# RS485.net
KiCad netlist of a schematic drawn in Altium Designer
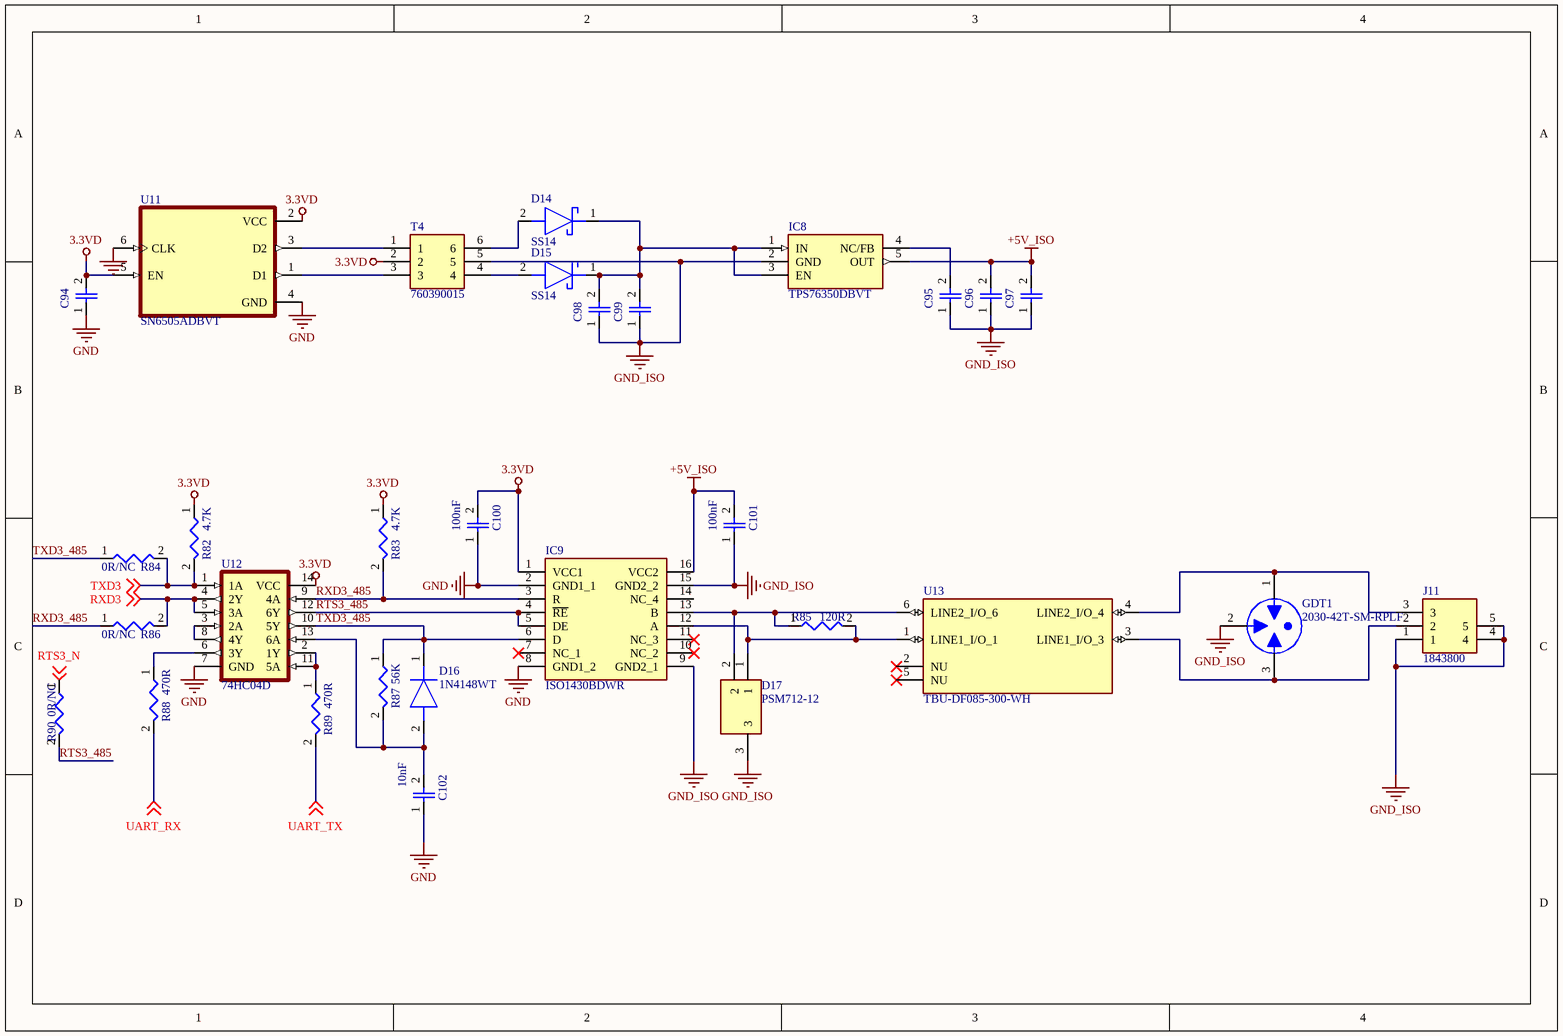
[diagram p0: RS485.SchDoc]

(export (version "E")
  (design (tool "Eeschema 10.0.6"))
  (components
    (comp (ref "C94")
      (value "10uF,0805")
      (footprint "0805-C")
      (libsource (lib "OOLITEV8_0_2-DEV-V1_1_17") (part "CAP"))
    )
    (comp (ref "C95")
      (value "10nF,0603/NC")
      (footprint "0603-C")
      (libsource (lib "OOLITEV8_0_2-DEV-V1_1_17") (part "CAP"))
    )
    (comp (ref "C96")
      (value "10uF,0805")
      (footprint "0805-C")
      (libsource (lib "OOLITEV8_0_2-DEV-V1_1_17") (part "CAP"))
    )
    (comp (ref "C97")
      (value "0.1uF,0603")
      (footprint "0603-C")
      (libsource (lib "OOLITEV8_0_2-DEV-V1_1_17") (part "CAP"))
    )
    (comp (ref "C98")
      (value "10uF,0805")
      (footprint "0805-C")
      (libsource (lib "OOLITEV8_0_2-DEV-V1_1_17") (part "CAP"))
    )
    (comp (ref "C99")
      (value "0.1uF,0603")
      (footprint "0603-C")
      (libsource (lib "OOLITEV8_0_2-DEV-V1_1_17") (part "CAP"))
    )
    (comp (ref "C100")
      (value "100nF")
      (footprint "0603-C")
      (libsource (lib "OOLITEV8_0_2-DEV-V1_1_17") (part "CAP"))
    )
    (comp (ref "C101")
      (value "100nF")
      (footprint "0603-C")
      (libsource (lib "OOLITEV8_0_2-DEV-V1_1_17") (part "CAP"))
    )
    (comp (ref "C102")
      (value "10nF")
      (footprint "0603-C")
      (libsource (lib "OOLITEV8_0_2-DEV-V1_1_17") (part "CAP"))
    )
    (comp (ref "D14")
      (value "SS14")
      (footprint "SamacSys:DIOM5127X261N")
      (description "Schottky Diode")
      (libsource (lib "*") (part "SS14"))
    )
    (comp (ref "D15")
      (value "SS14")
      (footprint "SamacSys:DIOM5127X261N")
      (description "Schottky Diode")
      (libsource (lib "*") (part "SS14"))
    )
    (comp (ref "D16")
      (value "1N4148WT")
      (footprint "SamacSys:SODFL1608X70N")
      (description "Diode")
      (libsource (lib "*") (part "1N4148WT"))
    )
    (comp (ref "D17")
      (value "PSM712-12")
      (footprint "SamacSys:PSM71212")
      (description "TVS Diode (Bi-directional)")
      (libsource (lib "*") (part "PSM712-12"))
    )
    (comp (ref "GDT1")
      (value "2030-42T-SM-RPLF")
      (footprint "2030-42T-SM-RPLF")
      (description "Gas Discharge Tube 90V 10000A _10kA_ 3 Pole Through Hole")
      (fields (field (name "MF") "Littelfuse Inc.") (field (name "MP") "SL1021A090R"))
      (libsource (lib "2030-42T-SM-RPLF") (part "2030-42T-SM-RPLF"))
    )
    (comp (ref "IC8")
      (value "TPS76350DBVT")
      (footprint "SamacSys:SOT95P280X145-5N")
      (description "Integrated Circuit")
      (fields (field (name "MOUSER PART NUMBER") "595-TPS76350DBVT"))
      (libsource (lib "*") (part "TPS76350DBVT"))
    )
    (comp (ref "IC9")
      (value "ISO1430BDWR")
      (footprint "SamacSys:SOIC127P1030X265-16N")
      (description "Integrated Circuit")
      (fields (field (name "MOUSER PART NUMBER") "595-ISO1430BDWR"))
      (libsource (lib "*") (part "ISO1430BDWR"))
    )
    (comp (ref "J11")
      (value "1843800")
      (footprint "SamacSys:1843800")
      (description "Connector")
      (fields (field (name "MOUSER PART NUMBER") "651-1843800"))
      (libsource (lib "*") (part "1843800"))
    )
    (comp (ref "R82")
      (value "4.7K")
      (footprint "0603-R")
      (libsource (lib "OOLITEV8_0_2-DEV-V1_1_17") (part "Res"))
    )
    (comp (ref "R83")
      (value "4.7K")
      (footprint "0603-R")
      (libsource (lib "OOLITEV8_0_2-DEV-V1_1_17") (part "Res"))
    )
    (comp (ref "R84")
      (value "0R/NC")
      (footprint "0603-R")
      (libsource (lib "OOLITEV8_0_2-DEV-V1_1_17") (part "Res"))
    )
    (comp (ref "R85")
      (value "120R")
      (footprint "0603-R")
      (libsource (lib "OOLITEV8_0_2-DEV-V1_1_17") (part "Res"))
    )
    (comp (ref "R86")
      (value "0R/NC")
      (footprint "0603-R")
      (libsource (lib "OOLITEV8_0_2-DEV-V1_1_17") (part "Res"))
    )
    (comp (ref "R87")
      (value "56K")
      (footprint "0603-R")
      (libsource (lib "OOLITEV8_0_2-DEV-V1_1_17") (part "Res"))
    )
    (comp (ref "R88")
      (value "470R")
      (footprint "0603-R")
      (libsource (lib "OOLITEV8_0_2-DEV-V1_1_17") (part "Res"))
    )
    (comp (ref "R89")
      (value "470R")
      (footprint "0603-R")
      (libsource (lib "OOLITEV8_0_2-DEV-V1_1_17") (part "Res"))
    )
    (comp (ref "R90")
      (value "0R/NC")
      (footprint "0603-R")
      (libsource (lib "OOLITEV8_0_2-DEV-V1_1_17") (part "Res"))
    )
    (comp (ref "T4")
      (value "760390015")
      (footprint "SamacSys:760390015")
      (description "Transformer")
      (fields (field (name "MOUSER PART NUMBER") "710-760390015"))
      (libsource (lib "*") (part "760390015"))
    )
    (comp (ref "U11")
      (value "SN6505ADBVT")
      (footprint "SOT95P280X145-6N")
      (fields
        (field (name "MF") "Texas Instruments")
        (field (name "BUYPART") "https://www.snapeda.com/parts/SN6505ADBVT/Texas%20Instruments/view-part/779078/?ref=eda")
      )
      (libsource (lib "SN6505ADBVT") (part "SN6505ADBVT"))
    )
    (comp (ref "U12")
      (value "74HC04D")
      (footprint "SOIC127P600X175-14N")
      (description "Inverter IC 6 Channel 14-SOIC")
      (fields (field (name "MF") "Toshiba"))
      (libsource (lib "74HC04D") (part "74HC04D"))
    )
    (comp (ref "U13")
      (value "TBU-DF085-300-WH")
      (footprint "IC_TBU-DF085-300-WH")
      (description "DUAL BI-DIR TBU 850V 300MA")
      (fields (field (name "MF") "Bourns Inc."))
      (libsource (lib "TBU-DF085-300-WH") (part "TBU-DF085-300-WH"))
    )
  )
  (nets
    (net (code "1") (name "+5V_ISO") (class "Default")
      (node (ref "C101") (pin "2") (pinfunction "2_2") (pintype "passive"))
      (node (ref "C96") (pin "2") (pinfunction "2_2") (pintype "passive"))
      (node (ref "C97") (pin "2") (pinfunction "2_2") (pintype "passive"))
      (node (ref "IC8") (pin "5") (pinfunction "OUT_5") (pintype "output"))
      (node (ref "IC9") (pin "16") (pinfunction "VCC2_16") (pintype "passive"))
    )
    (net (code "2") (name "/RTS3_485") (class "Default")
      (node (ref "IC9") (pin "4") (pinfunction "~{RE}_4") (pintype "passive"))
      (node (ref "IC9") (pin "5") (pinfunction "DE_5") (pintype "passive"))
      (node (ref "R90") (pin "2") (pinfunction "2_2") (pintype "passive"))
      (node (ref "U12") (pin "12") (pinfunction "6Y_12") (pintype "output"))
    )
    (net (code "3") (name "/RXD3_485") (class "Default")
      (node (ref "IC9") (pin "3") (pinfunction "R_3") (pintype "passive"))
      (node (ref "R83") (pin "2") (pinfunction "2_2") (pintype "passive"))
      (node (ref "R86") (pin "1") (pinfunction "1_1") (pintype "passive"))
      (node (ref "U12") (pin "9") (pinfunction "4A_9") (pintype "input"))
    )
    (net (code "4") (name "/TXD3_485") (class "Default")
      (node (ref "D16") (pin "1") (pinfunction "K_1") (pintype "passive"))
      (node (ref "IC9") (pin "6") (pinfunction "D_6") (pintype "passive"))
      (node (ref "R84") (pin "1") (pinfunction "1_1") (pintype "passive"))
      (node (ref "R87") (pin "1") (pinfunction "1_1") (pintype "passive"))
      (node (ref "U12") (pin "10") (pinfunction "5Y_10") (pintype "output"))
    )
    (net (code "5") (name "3.3VD") (class "Default")
      (node (ref "C100") (pin "2") (pinfunction "2_2") (pintype "passive"))
      (node (ref "C94") (pin "2") (pinfunction "2_2") (pintype "passive"))
      (node (ref "IC9") (pin "1") (pinfunction "VCC1_1") (pintype "passive"))
      (node (ref "R82") (pin "1") (pinfunction "1_1") (pintype "passive"))
      (node (ref "R83") (pin "1") (pinfunction "1_1") (pintype "passive"))
      (node (ref "T4") (pin "2") (pinfunction "2_2") (pintype "passive"))
      (node (ref "U11") (pin "2") (pinfunction "VCC_2") (pintype "power_in"))
      (node (ref "U11") (pin "5") (pinfunction "EN_5") (pintype "input"))
      (node (ref "U12") (pin "14") (pinfunction "VCC_14") (pintype "power_in"))
    )
    (net (code "6") (name "GND") (class "Default")
      (node (ref "C100") (pin "1") (pinfunction "1_1") (pintype "passive"))
      (node (ref "C102") (pin "1") (pinfunction "1_1") (pintype "passive"))
      (node (ref "C94") (pin "1") (pinfunction "1_1") (pintype "passive"))
      (node (ref "IC9") (pin "2") (pinfunction "GND1_1_2") (pintype "passive"))
      (node (ref "IC9") (pin "8") (pinfunction "GND1_2_8") (pintype "passive"))
      (node (ref "U11") (pin "4") (pinfunction "GND_4") (pintype "power_in"))
      (node (ref "U11") (pin "6") (pinfunction "CLK_6") (pintype "input"))
      (node (ref "U12") (pin "7") (pinfunction "GND_7") (pintype "passive"))
    )
    (net (code "7") (name "GND_ISO") (class "Default")
      (node (ref "C101") (pin "1") (pinfunction "1_1") (pintype "passive"))
      (node (ref "C95") (pin "1") (pinfunction "1_1") (pintype "passive"))
      (node (ref "C96") (pin "1") (pinfunction "1_1") (pintype "passive"))
      (node (ref "C97") (pin "1") (pinfunction "1_1") (pintype "passive"))
      (node (ref "C98") (pin "1") (pinfunction "1_1") (pintype "passive"))
      (node (ref "C99") (pin "1") (pinfunction "1_1") (pintype "passive"))
      (node (ref "D17") (pin "3") (pinfunction "3_3") (pintype "passive"))
      (node (ref "GDT1") (pin "2") (pinfunction "E_2") (pintype "passive"))
      (node (ref "IC8") (pin "2") (pinfunction "GND_2") (pintype "power_in"))
      (node (ref "IC9") (pin "15") (pinfunction "GND2_2_15") (pintype "passive"))
      (node (ref "IC9") (pin "9") (pinfunction "GND2_1_9") (pintype "passive"))
      (node (ref "J11") (pin "1") (pinfunction "1_1") (pintype "passive"))
      (node (ref "J11") (pin "4") (pinfunction "4_4") (pintype "passive"))
      (node (ref "J11") (pin "5") (pinfunction "5_5") (pintype "passive"))
      (node (ref "T4") (pin "5") (pinfunction "5_5") (pintype "passive"))
    )
    (net (code "8") (name "Net-(D14-A)") (class "Default")
      (node (ref "D14") (pin "2") (pinfunction "A_2") (pintype "passive"))
      (node (ref "T4") (pin "6") (pinfunction "6_6") (pintype "passive"))
    )
    (net (code "9") (name "Net-(D14-K)") (class "Default")
      (node (ref "C98") (pin "2") (pinfunction "2_2") (pintype "passive"))
      (node (ref "C99") (pin "2") (pinfunction "2_2") (pintype "passive"))
      (node (ref "D14") (pin "1") (pinfunction "K_1") (pintype "passive"))
      (node (ref "D15") (pin "1") (pinfunction "K_1") (pintype "passive"))
      (node (ref "IC8") (pin "1") (pinfunction "IN_1") (pintype "input"))
      (node (ref "IC8") (pin "3") (pinfunction "EN_3") (pintype "passive"))
    )
    (net (code "10") (name "Net-(D15-A)") (class "Default")
      (node (ref "D15") (pin "2") (pinfunction "A_2") (pintype "passive"))
      (node (ref "T4") (pin "4") (pinfunction "4_4") (pintype "passive"))
    )
    (net (code "11") (name "Net-(D16-A)") (class "Default")
      (node (ref "C102") (pin "2") (pinfunction "2_2") (pintype "passive"))
      (node (ref "D16") (pin "2") (pinfunction "A_2") (pintype "passive"))
      (node (ref "R87") (pin "2") (pinfunction "2_2") (pintype "passive"))
      (node (ref "U12") (pin "13") (pinfunction "6A_13") (pintype "input"))
    )
    (net (code "12") (name "Net-(GDT1-A)") (class "Default")
      (node (ref "GDT1") (pin "1") (pinfunction "A_1") (pintype "passive"))
      (node (ref "J11") (pin "3") (pinfunction "3_3") (pintype "passive"))
      (node (ref "U13") (pin "4") (pinfunction "LINE2_I/O_4_4") (pintype "bidirectional"))
    )
    (net (code "13") (name "Net-(GDT1-B)") (class "Default")
      (node (ref "GDT1") (pin "3") (pinfunction "B_3") (pintype "passive"))
      (node (ref "J11") (pin "2") (pinfunction "2_2") (pintype "passive"))
      (node (ref "U13") (pin "3") (pinfunction "LINE1_I/O_3_3") (pintype "bidirectional"))
    )
    (net (code "14") (name "Net-(IC8-NC{slash}FB)") (class "Default")
      (node (ref "C95") (pin "2") (pinfunction "2_2") (pintype "passive"))
      (node (ref "IC8") (pin "4") (pinfunction "NC/FB_4") (pintype "passive"))
    )
    (net (code "15") (name "Net-(IC9-A)") (class "Default")
      (node (ref "D17") (pin "1") (pinfunction "1_1") (pintype "passive"))
      (node (ref "IC9") (pin "12") (pinfunction "A_12") (pintype "passive"))
      (node (ref "R85") (pin "2") (pinfunction "2_2") (pintype "passive"))
      (node (ref "U13") (pin "1") (pinfunction "LINE1_I/O_1_1") (pintype "bidirectional"))
    )
    (net (code "16") (name "Net-(IC9-B)") (class "Default")
      (node (ref "D17") (pin "2") (pinfunction "2_2") (pintype "passive"))
      (node (ref "IC9") (pin "13") (pinfunction "B_13") (pintype "passive"))
      (node (ref "R85") (pin "1") (pinfunction "1_1") (pintype "passive"))
      (node (ref "U13") (pin "6") (pinfunction "LINE2_I/O_6_6") (pintype "bidirectional"))
    )
    (net (code "17") (name "Net-(U11-D1)") (class "Default")
      (node (ref "T4") (pin "3") (pinfunction "3_3") (pintype "passive"))
      (node (ref "U11") (pin "1") (pinfunction "D1_1") (pintype "output"))
    )
    (net (code "18") (name "Net-(U11-D2)") (class "Default")
      (node (ref "T4") (pin "1") (pinfunction "1_1") (pintype "passive"))
      (node (ref "U11") (pin "3") (pinfunction "D2_3") (pintype "output"))
    )
    (net (code "19") (name "Net-(U12-1Y)") (class "Default")
      (node (ref "R89") (pin "1") (pinfunction "1_1") (pintype "passive"))
      (node (ref "U12") (pin "11") (pinfunction "5A_11") (pintype "input"))
      (node (ref "U12") (pin "2") (pinfunction "1Y_2") (pintype "output"))
    )
    (net (code "20") (name "Net-(U12-2A)") (class "Default")
      (node (ref "U12") (pin "3") (pinfunction "2A_3") (pintype "input"))
      (node (ref "U12") (pin "8") (pinfunction "4Y_8") (pintype "output"))
    )
    (net (code "21") (name "Net-(U12-3Y)") (class "Default")
      (node (ref "R88") (pin "1") (pinfunction "1_1") (pintype "passive"))
      (node (ref "U12") (pin "6") (pinfunction "3Y_6") (pintype "output"))
    )
    (net (code "22") (name "RTS3_N") (class "Default")
      (node (ref "R90") (pin "1") (pinfunction "1_1") (pintype "passive"))
    )
    (net (code "23") (name "RXD3") (class "Default")
      (node (ref "R86") (pin "2") (pinfunction "2_2") (pintype "passive"))
      (node (ref "U12") (pin "4") (pinfunction "2Y_4") (pintype "output"))
      (node (ref "U12") (pin "5") (pinfunction "3A_5") (pintype "input"))
    )
    (net (code "24") (name "TXD3") (class "Default")
      (node (ref "R82") (pin "2") (pinfunction "2_2") (pintype "passive"))
      (node (ref "R84") (pin "2") (pinfunction "2_2") (pintype "passive"))
      (node (ref "U12") (pin "1") (pinfunction "1A_1") (pintype "input"))
    )
    (net (code "25") (name "UART_RX") (class "Default")
      (node (ref "R88") (pin "2") (pinfunction "2_2") (pintype "passive"))
    )
    (net (code "26") (name "UART_TX") (class "Default")
      (node (ref "R89") (pin "2") (pinfunction "2_2") (pintype "passive"))
    )
    (net (code "27") (name "unconnected-(IC9-NC_1-Pad7)") (class "Default")
      (node (ref "IC9") (pin "7") (pinfunction "NC_1_7") (pintype "passive+no_connect"))
    )
    (net (code "28") (name "unconnected-(IC9-NC_2-Pad10)") (class "Default")
      (node (ref "IC9") (pin "10") (pinfunction "NC_2_10") (pintype "passive+no_connect"))
    )
    (net (code "29") (name "unconnected-(IC9-NC_3-Pad11)") (class "Default")
      (node (ref "IC9") (pin "11") (pinfunction "NC_3_11") (pintype "passive+no_connect"))
    )
    (net (code "30") (name "unconnected-(IC9-NC_4-Pad14)") (class "Default")
      (node (ref "IC9") (pin "14") (pinfunction "NC_4_14") (pintype "passive"))
    )
    (net (code "31") (name "unconnected-(U13-NU-Pad2)") (class "Default")
      (node (ref "U13") (pin "2") (pinfunction "NU_2") (pintype "passive+no_connect"))
    )
    (net (code "32") (name "unconnected-(U13-NU-Pad5)") (class "Default")
      (node (ref "U13") (pin "5") (pinfunction "NU_5") (pintype "passive+no_connect"))
    )
  )
)
